# INA180_Breakout.net
KiCad netlist of a schematic drawn in Altium Designer
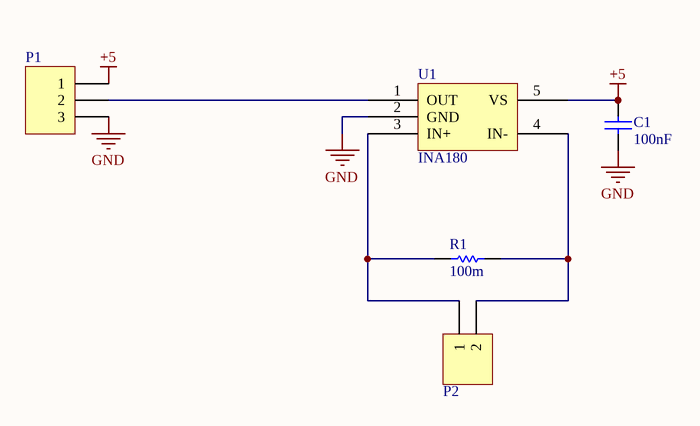
[diagram p0: INA180_Breakout.SchDoc]

(export (version "E")
  (design (tool "Eeschema 10.0.6"))
  (components
    (comp (ref "C1")
      (value "100nF")
      (footprint "0805 - Capacitor")
      (description "Nonpolarized Capacitor")
      (fields
        (field (name "MANUFACTURER") "Yageo")
        (field (name "MANUFACTURER PART NUMBER") "CC0805KRX7R9BB104")
      )
      (libsource (lib "General") (part "Capacitor - Nonpolarized"))
    )
    (comp (ref "P1")
      (value "1x3 Header")
      (footprint "HDR1X3")
      (description "1x3 Pin Header")
      (libsource (lib "GeneralConnectors") (part "1x3 Header"))
    )
    (comp (ref "P2")
      (value "1x2 Header")
      (footprint "HDR1X2")
      (description "1x2 Pin Header")
      (libsource (lib "GeneralConnectors") (part "1x2 Header"))
    )
    (comp (ref "R1")
      (value "100m")
      (footprint "0603 - Resistor")
      (description "Resistor")
      (fields (field (name "MANUFACTURER PART NUMBER") "73L3R10J") (field (name "MANUFACTURER") "CTS"))
      (libsource (lib "General") (part "Resistor"))
    )
    (comp (ref "U1")
      (value "INA180")
      (footprint "INA180")
      (description "0V to 26V Current Sense Amplifier")
      (fields
        (field (name "MANUFACTURER") "Texas Instruments")
        (field (name "MANUFACTURER PART NUMBER") "INA180A2IDBVR")
      )
      (libsource (lib "GeneralComponents") (part "INA180"))
    )
  )
  (nets
    (net (code "1") (name "+5") (class "Default")
      (node (ref "C1") (pin "2") (pinfunction "2_2") (pintype "passive"))
      (node (ref "P1") (pin "1") (pinfunction "1_1") (pintype "passive"))
      (node (ref "U1") (pin "5") (pinfunction "VS_5") (pintype "passive"))
    )
    (net (code "2") (name "GND") (class "Default")
      (node (ref "C1") (pin "1") (pinfunction "1_1") (pintype "passive"))
      (node (ref "P1") (pin "3") (pinfunction "3_3") (pintype "passive"))
      (node (ref "U1") (pin "2") (pinfunction "GND_2") (pintype "passive"))
    )
    (net (code "3") (name "Net-(U1-IN+)") (class "Default")
      (node (ref "P2") (pin "1") (pinfunction "1_1") (pintype "passive"))
      (node (ref "R1") (pin "1") (pinfunction "1_1") (pintype "passive"))
      (node (ref "U1") (pin "3") (pinfunction "IN+_3") (pintype "passive"))
    )
    (net (code "4") (name "Net-(U1-IN-)") (class "Default")
      (node (ref "P2") (pin "2") (pinfunction "2_2") (pintype "passive"))
      (node (ref "R1") (pin "2") (pinfunction "2_2") (pintype "passive"))
      (node (ref "U1") (pin "4") (pinfunction "IN-_4") (pintype "passive"))
    )
    (net (code "5") (name "Net-(U1-OUT)") (class "Default")
      (node (ref "P1") (pin "2") (pinfunction "2_2") (pintype "passive"))
      (node (ref "U1") (pin "1") (pinfunction "OUT_1") (pintype "passive"))
    )
  )
)
